# V4-AddOnZigbee-SMD-V006.net
KiCad netlist of a schematic drawn in EAGLE
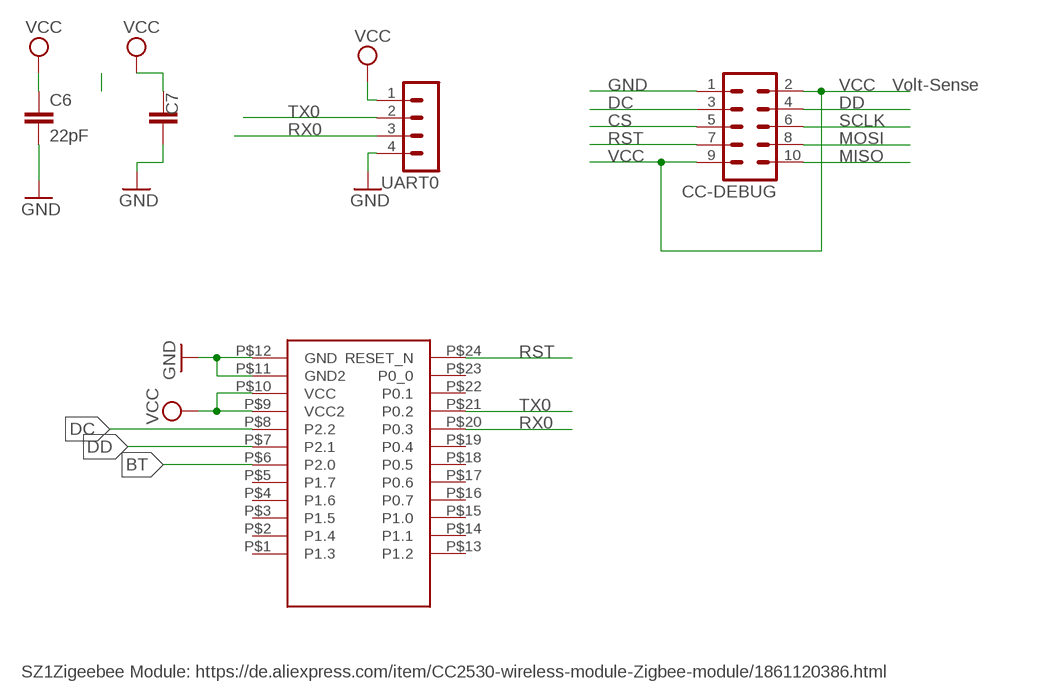
[diagram p0: schematic, sheet 1]

(export (version "E")
  (design (tool "Eeschema 10.0.6"))
  (components
    (comp (ref "C6")
      (value "22pF")
      (footprint "eagle-import:C0805")
      (libsource (lib "eagle-import") (part "C-EUC0805"))
    )
    (comp (ref "C7")
      (value "C-EUC1812")
      (footprint "eagle-import:C1812")
      (libsource (lib "eagle-import") (part "C-EUC1812"))
    )
    (comp (ref "CC-DEBUG")
      (value "MA05-2")
      (footprint "eagle-import:MA05-2")
      (libsource (lib "eagle-import") (part "MA05-2"))
    )
    (comp (ref "U$1")
      (value "CC2530")
      (footprint "eagle-import:SZ1ZIGBEE-SMD")
      (libsource (lib "eagle-import") (part "CC2530"))
    )
    (comp (ref "UART0")
      (value "MA04-1")
      (footprint "eagle-import:MA04-1")
      (libsource (lib "eagle-import") (part "MA04-1"))
    )
  )
  (nets
    (net (code "1") (name "/CS") (class "Default")
      (node (ref "CC-DEBUG") (pin "5") (pinfunction "5_5") (pintype "passive"))
    )
    (net (code "2") (name "/MISO") (class "Default")
      (node (ref "CC-DEBUG") (pin "10") (pinfunction "10_10") (pintype "passive"))
    )
    (net (code "3") (name "/MOSI") (class "Default")
      (node (ref "CC-DEBUG") (pin "8") (pinfunction "8_8") (pintype "passive"))
    )
    (net (code "4") (name "/RST") (class "Default")
      (node (ref "CC-DEBUG") (pin "7") (pinfunction "7_7") (pintype "passive"))
      (node (ref "U$1") (pin "P$24") (pinfunction "RESET_N_P$24") (pintype "bidirectional"))
    )
    (net (code "5") (name "/RX0") (class "Default")
      (node (ref "U$1") (pin "P$20") (pinfunction "P0.3_P$20") (pintype "bidirectional"))
      (node (ref "UART0") (pin "3") (pinfunction "3_3") (pintype "passive"))
    )
    (net (code "6") (name "/SCLK") (class "Default")
      (node (ref "CC-DEBUG") (pin "6") (pinfunction "6_6") (pintype "passive"))
    )
    (net (code "7") (name "/TX0") (class "Default")
      (node (ref "U$1") (pin "P$21") (pinfunction "P0.2_P$21") (pintype "bidirectional"))
      (node (ref "UART0") (pin "2") (pinfunction "2_2") (pintype "passive"))
    )
    (net (code "8") (name "BT") (class "Default")
      (node (ref "U$1") (pin "P$6") (pinfunction "P2.0_P$6") (pintype "bidirectional"))
    )
    (net (code "9") (name "DC") (class "Default")
      (node (ref "CC-DEBUG") (pin "3") (pinfunction "3_3") (pintype "passive"))
      (node (ref "U$1") (pin "P$8") (pinfunction "P2.2_P$8") (pintype "bidirectional"))
    )
    (net (code "10") (name "DD") (class "Default")
      (node (ref "CC-DEBUG") (pin "4") (pinfunction "4_4") (pintype "passive"))
      (node (ref "U$1") (pin "P$7") (pinfunction "P2.1_P$7") (pintype "bidirectional"))
    )
    (net (code "11") (name "GND") (class "Default")
      (node (ref "C6") (pin "2") (pinfunction "2_2") (pintype "passive"))
      (node (ref "C7") (pin "1") (pinfunction "1_1") (pintype "passive"))
      (node (ref "CC-DEBUG") (pin "1") (pinfunction "1_1") (pintype "passive"))
      (node (ref "U$1") (pin "P$11") (pinfunction "GND2_P$11") (pintype "bidirectional"))
      (node (ref "U$1") (pin "P$12") (pinfunction "GND_P$12") (pintype "bidirectional"))
      (node (ref "UART0") (pin "4") (pinfunction "4_4") (pintype "passive"))
    )
    (net (code "12") (name "VCC") (class "Default")
      (node (ref "C6") (pin "1") (pinfunction "1_1") (pintype "passive"))
      (node (ref "C7") (pin "2") (pinfunction "2_2") (pintype "passive"))
      (node (ref "CC-DEBUG") (pin "2") (pinfunction "2_2") (pintype "passive"))
      (node (ref "CC-DEBUG") (pin "9") (pinfunction "9_9") (pintype "passive"))
      (node (ref "U$1") (pin "P$10") (pinfunction "VCC_P$10") (pintype "bidirectional"))
      (node (ref "U$1") (pin "P$9") (pinfunction "VCC2_P$9") (pintype "bidirectional"))
      (node (ref "UART0") (pin "1") (pinfunction "1_1") (pintype "passive"))
    )
    (net (code "13") (name "unconnected-(U$1-P0.1-PadP$22)") (class "Default")
      (node (ref "U$1") (pin "P$22") (pinfunction "P0.1_P$22") (pintype "bidirectional"))
    )
    (net (code "14") (name "unconnected-(U$1-P0.4-PadP$19)") (class "Default")
      (node (ref "U$1") (pin "P$19") (pinfunction "P0.4_P$19") (pintype "bidirectional"))
    )
    (net (code "15") (name "unconnected-(U$1-P0.5-PadP$18)") (class "Default")
      (node (ref "U$1") (pin "P$18") (pinfunction "P0.5_P$18") (pintype "bidirectional"))
    )
    (net (code "16") (name "unconnected-(U$1-P0.6-PadP$17)") (class "Default")
      (node (ref "U$1") (pin "P$17") (pinfunction "P0.6_P$17") (pintype "bidirectional"))
    )
    (net (code "17") (name "unconnected-(U$1-P0.7-PadP$16)") (class "Default")
      (node (ref "U$1") (pin "P$16") (pinfunction "P0.7_P$16") (pintype "bidirectional"))
    )
    (net (code "18") (name "unconnected-(U$1-P0_0-PadP$23)") (class "Default")
      (node (ref "U$1") (pin "P$23") (pinfunction "P0_0_P$23") (pintype "bidirectional"))
    )
    (net (code "19") (name "unconnected-(U$1-P1.0-PadP$15)") (class "Default")
      (node (ref "U$1") (pin "P$15") (pinfunction "P1.0_P$15") (pintype "bidirectional"))
    )
    (net (code "20") (name "unconnected-(U$1-P1.1-PadP$14)") (class "Default")
      (node (ref "U$1") (pin "P$14") (pinfunction "P1.1_P$14") (pintype "bidirectional"))
    )
    (net (code "21") (name "unconnected-(U$1-P1.2-PadP$13)") (class "Default")
      (node (ref "U$1") (pin "P$13") (pinfunction "P1.2_P$13") (pintype "bidirectional"))
    )
    (net (code "22") (name "unconnected-(U$1-P1.3-PadP$1)") (class "Default")
      (node (ref "U$1") (pin "P$1") (pinfunction "P1.3_P$1") (pintype "bidirectional"))
    )
    (net (code "23") (name "unconnected-(U$1-P1.4-PadP$2)") (class "Default")
      (node (ref "U$1") (pin "P$2") (pinfunction "P1.4_P$2") (pintype "bidirectional"))
    )
    (net (code "24") (name "unconnected-(U$1-P1.5-PadP$3)") (class "Default")
      (node (ref "U$1") (pin "P$3") (pinfunction "P1.5_P$3") (pintype "bidirectional"))
    )
    (net (code "25") (name "unconnected-(U$1-P1.6-PadP$4)") (class "Default")
      (node (ref "U$1") (pin "P$4") (pinfunction "P1.6_P$4") (pintype "bidirectional"))
    )
    (net (code "26") (name "unconnected-(U$1-P1.7-PadP$5)") (class "Default")
      (node (ref "U$1") (pin "P$5") (pinfunction "P1.7_P$5") (pintype "bidirectional"))
    )
  )
)
